# Dummy.net
KiCad netlist of a schematic drawn in EAGLE
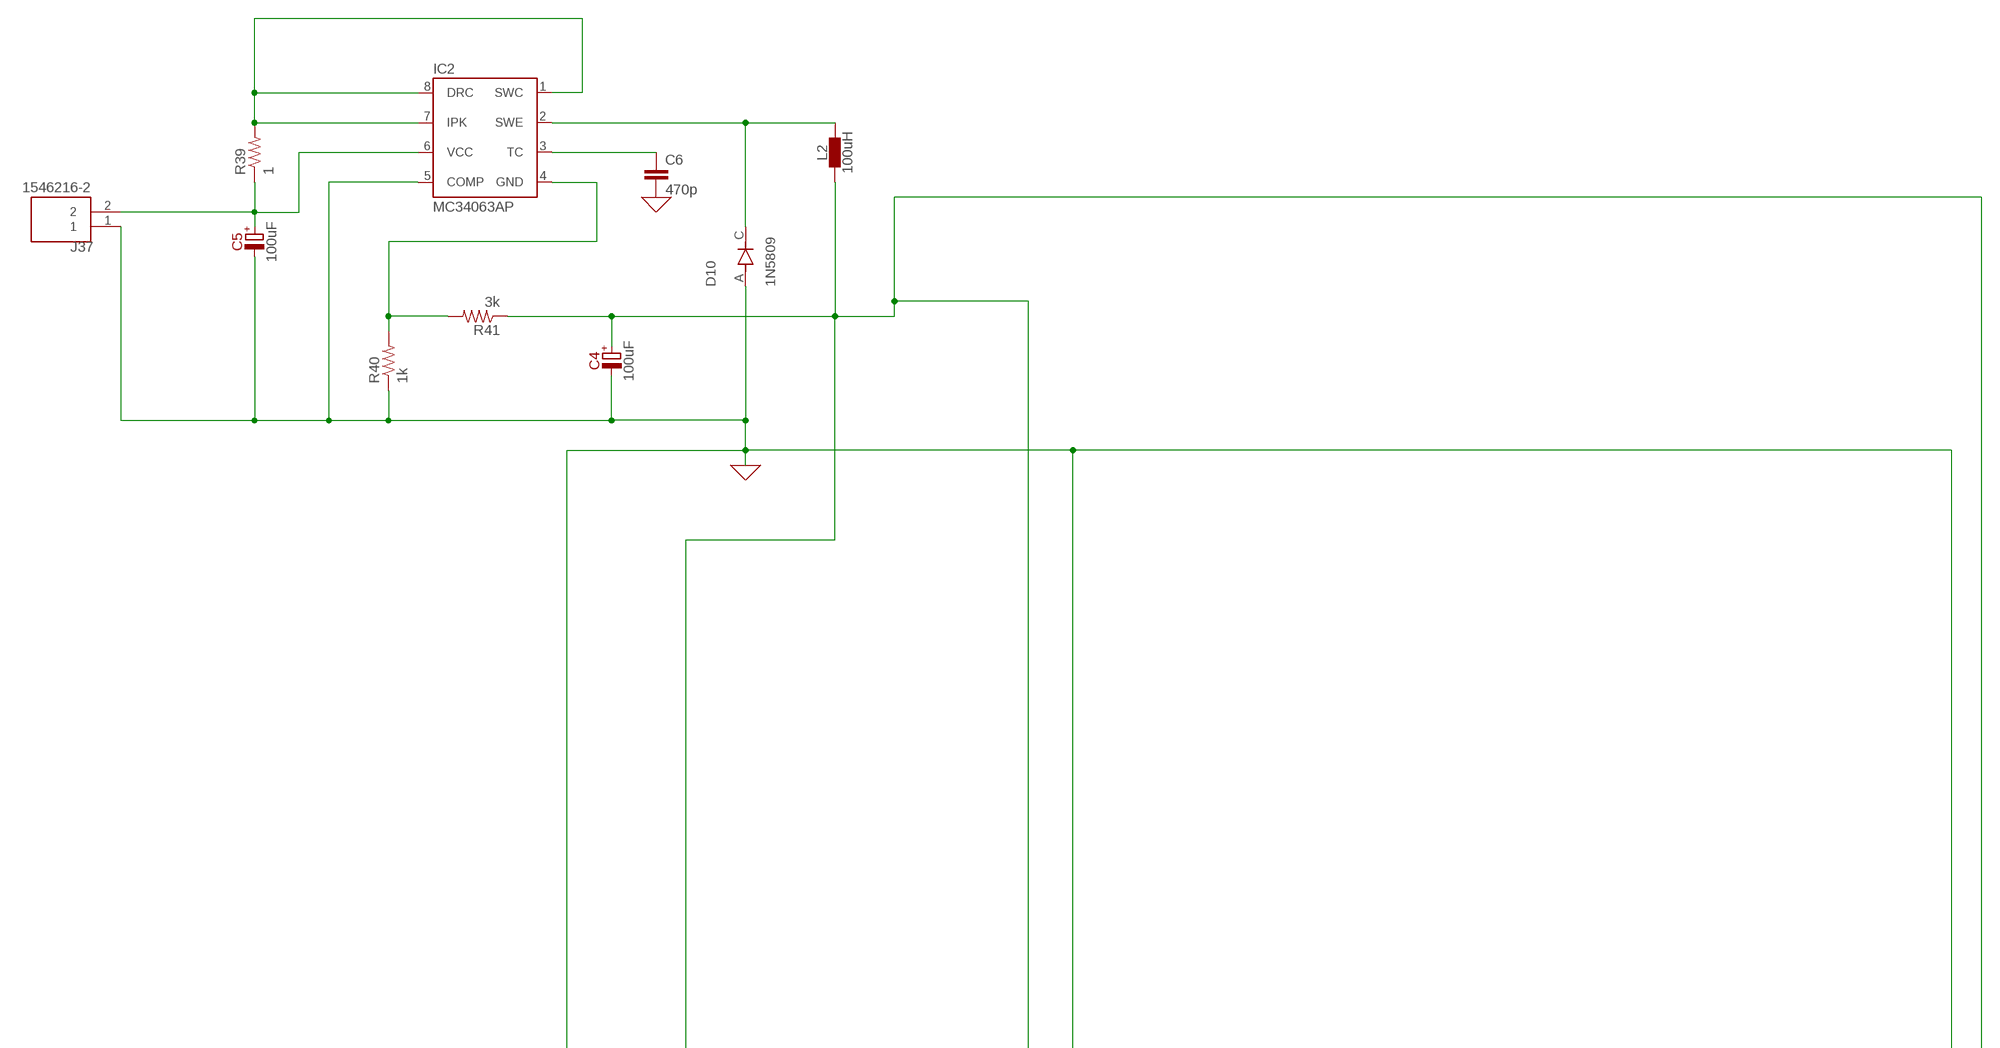
[diagram p0: schematic, sheet 1, part 1 of 3]
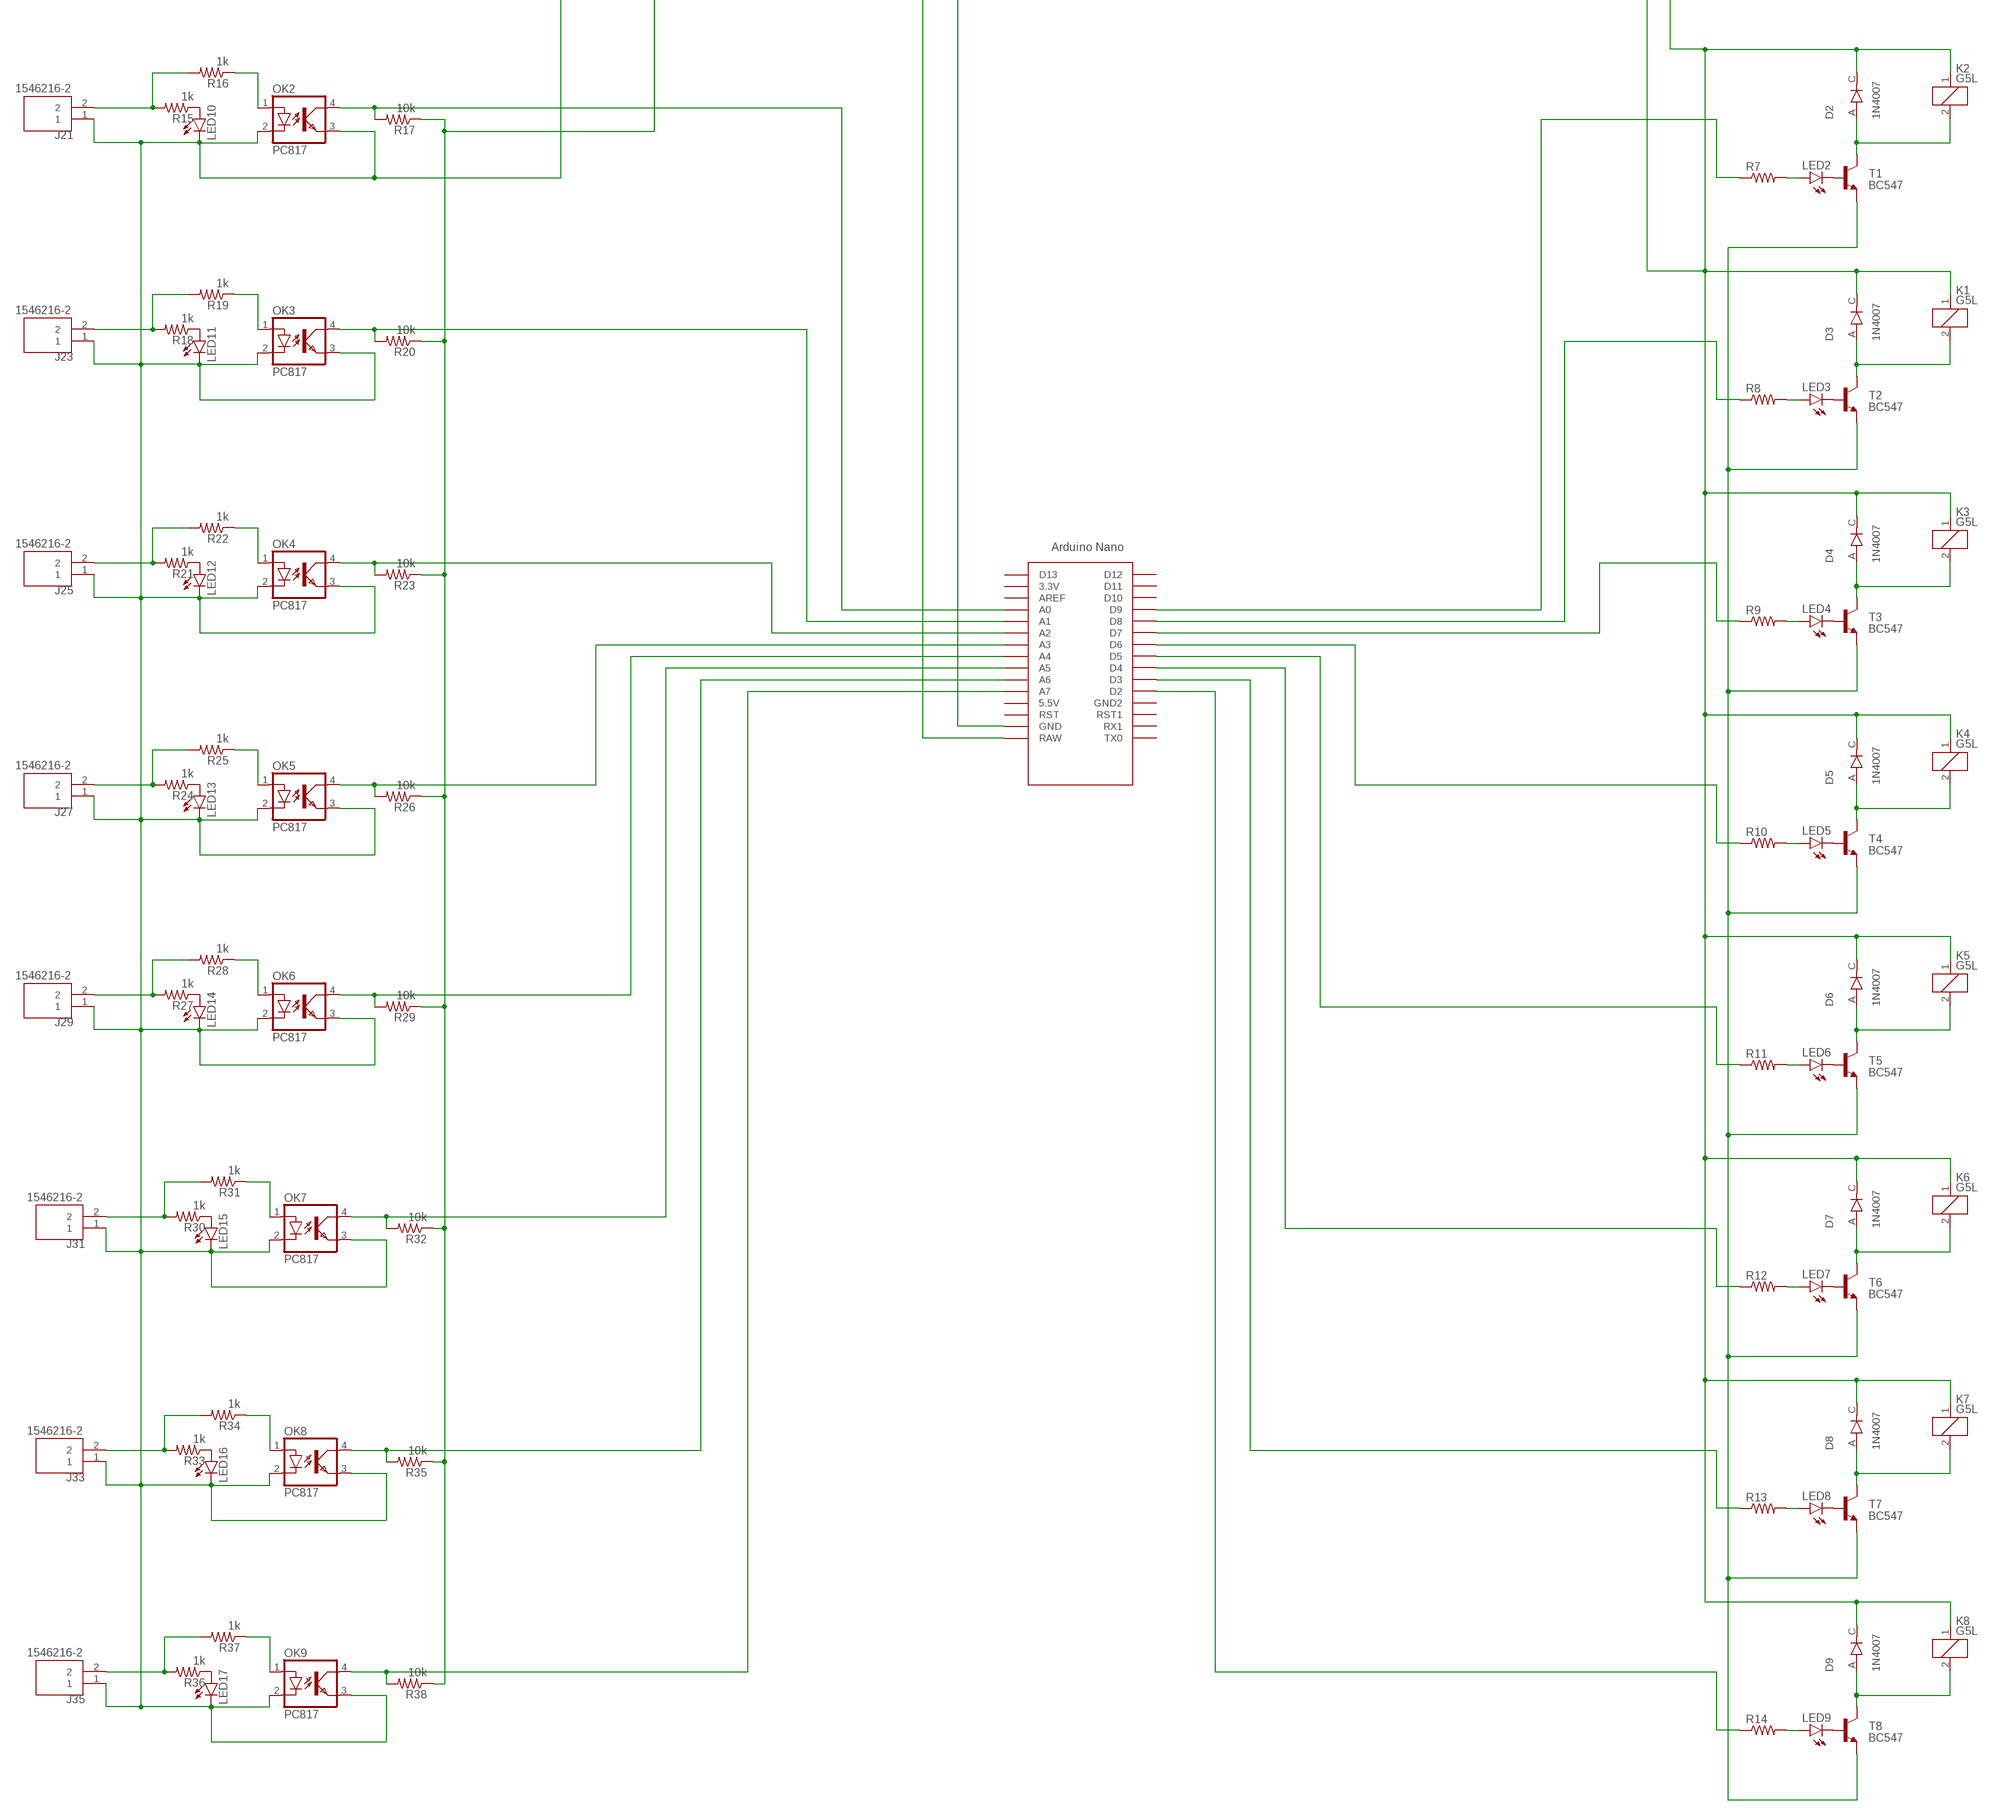
[diagram p1: schematic, sheet 1, part 2 of 3]
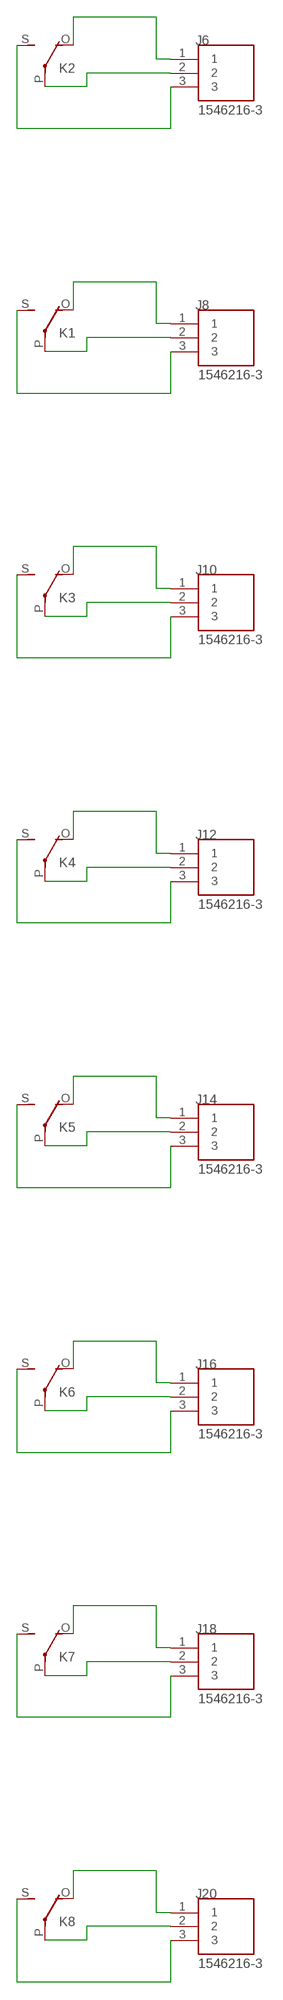
[diagram p2: schematic, sheet 1, part 3 of 3]

(export (version "E")
  (design (tool "Eeschema 10.0.6"))
  (components
    (comp (ref "C4")
      (value "100uF")
      (footprint "eagle-import:E1,5-4")
      (libsource (lib "eagle-import") (part "?1U/50V"))
    )
    (comp (ref "C5")
      (value "100uF")
      (footprint "eagle-import:E1,5-4")
      (libsource (lib "eagle-import") (part "?1U/50V"))
    )
    (comp (ref "C6")
      (value "470p")
      (footprint "eagle-import:C2.5-2")
      (libsource (lib "eagle-import") (part "C2.5/2"))
    )
    (comp (ref "D2")
      (value "1N4007")
      (footprint "eagle-import:DIOAD1060W80L520D270")
      (fields (field (name "MF") "ON Semiconductor"))
      (libsource (lib "eagle-import") (part "1N4007"))
    )
    (comp (ref "D3")
      (value "1N4007")
      (footprint "eagle-import:DIOAD1060W80L520D270")
      (fields (field (name "MF") "ON Semiconductor"))
      (libsource (lib "eagle-import") (part "1N4007"))
    )
    (comp (ref "D4")
      (value "1N4007")
      (footprint "eagle-import:DIOAD1060W80L520D270")
      (fields (field (name "MF") "ON Semiconductor"))
      (libsource (lib "eagle-import") (part "1N4007"))
    )
    (comp (ref "D5")
      (value "1N4007")
      (footprint "eagle-import:DIOAD1060W80L520D270")
      (fields (field (name "MF") "ON Semiconductor"))
      (libsource (lib "eagle-import") (part "1N4007"))
    )
    (comp (ref "D6")
      (value "1N4007")
      (footprint "eagle-import:DIOAD1060W80L520D270")
      (fields (field (name "MF") "ON Semiconductor"))
      (libsource (lib "eagle-import") (part "1N4007"))
    )
    (comp (ref "D7")
      (value "1N4007")
      (footprint "eagle-import:DIOAD1060W80L520D270")
      (fields (field (name "MF") "ON Semiconductor"))
      (libsource (lib "eagle-import") (part "1N4007"))
    )
    (comp (ref "D8")
      (value "1N4007")
      (footprint "eagle-import:DIOAD1060W80L520D270")
      (fields (field (name "MF") "ON Semiconductor"))
      (libsource (lib "eagle-import") (part "1N4007"))
    )
    (comp (ref "D9")
      (value "1N4007")
      (footprint "eagle-import:DIOAD1060W80L520D270")
      (fields (field (name "MF") "ON Semiconductor"))
      (libsource (lib "eagle-import") (part "1N4007"))
    )
    (comp (ref "D10")
      (value "1N5809")
      (footprint "eagle-import:DIOAD1060W80L520D270")
      (fields (field (name "MF") "ON Semiconductor") (field (name "MP") "1N4007"))
      (libsource (lib "eagle-import") (part "1N4007"))
    )
    (comp (ref "IC2")
      (value "MC34063AP")
      (footprint "eagle-import:DIL-08")
      (fields (field (name "MF") "Texas Instruments") (field (name "MP") "MC34063A"))
      (libsource (lib "eagle-import") (part "MC34063AP"))
    )
    (comp (ref "J6")
      (value "1546216-3")
      (footprint "eagle-import:TE_1546216-3")
      (fields (field (name "MF") "TE Connectivity"))
      (libsource (lib "eagle-import") (part "1546216-3"))
    )
    (comp (ref "J8")
      (value "1546216-3")
      (footprint "eagle-import:TE_1546216-3")
      (fields (field (name "MF") "TE Connectivity"))
      (libsource (lib "eagle-import") (part "1546216-3"))
    )
    (comp (ref "J10")
      (value "1546216-3")
      (footprint "eagle-import:TE_1546216-3")
      (fields (field (name "MF") "TE Connectivity"))
      (libsource (lib "eagle-import") (part "1546216-3"))
    )
    (comp (ref "J12")
      (value "1546216-3")
      (footprint "eagle-import:TE_1546216-3")
      (fields (field (name "MF") "TE Connectivity"))
      (libsource (lib "eagle-import") (part "1546216-3"))
    )
    (comp (ref "J14")
      (value "1546216-3")
      (footprint "eagle-import:TE_1546216-3")
      (fields (field (name "MF") "TE Connectivity"))
      (libsource (lib "eagle-import") (part "1546216-3"))
    )
    (comp (ref "J16")
      (value "1546216-3")
      (footprint "eagle-import:TE_1546216-3")
      (fields (field (name "MF") "TE Connectivity"))
      (libsource (lib "eagle-import") (part "1546216-3"))
    )
    (comp (ref "J18")
      (value "1546216-3")
      (footprint "eagle-import:TE_1546216-3")
      (fields (field (name "MF") "TE Connectivity"))
      (libsource (lib "eagle-import") (part "1546216-3"))
    )
    (comp (ref "J20")
      (value "1546216-3")
      (footprint "eagle-import:TE_1546216-3")
      (fields (field (name "MF") "TE Connectivity"))
      (libsource (lib "eagle-import") (part "1546216-3"))
    )
    (comp (ref "J21")
      (value "1546216-2")
      (footprint "eagle-import:TE_1546216-2")
      (fields (field (name "MF") "TE Connectivity"))
      (libsource (lib "eagle-import") (part "1546216-2"))
    )
    (comp (ref "J23")
      (value "1546216-2")
      (footprint "eagle-import:TE_1546216-2")
      (fields (field (name "MF") "TE Connectivity"))
      (libsource (lib "eagle-import") (part "1546216-2"))
    )
    (comp (ref "J25")
      (value "1546216-2")
      (footprint "eagle-import:TE_1546216-2")
      (fields (field (name "MF") "TE Connectivity"))
      (libsource (lib "eagle-import") (part "1546216-2"))
    )
    (comp (ref "J27")
      (value "1546216-2")
      (footprint "eagle-import:TE_1546216-2")
      (fields (field (name "MF") "TE Connectivity"))
      (libsource (lib "eagle-import") (part "1546216-2"))
    )
    (comp (ref "J29")
      (value "1546216-2")
      (footprint "eagle-import:TE_1546216-2")
      (fields (field (name "MF") "TE Connectivity"))
      (libsource (lib "eagle-import") (part "1546216-2"))
    )
    (comp (ref "J31")
      (value "1546216-2")
      (footprint "eagle-import:TE_1546216-2")
      (fields (field (name "MF") "TE Connectivity"))
      (libsource (lib "eagle-import") (part "1546216-2"))
    )
    (comp (ref "J33")
      (value "1546216-2")
      (footprint "eagle-import:TE_1546216-2")
      (fields (field (name "MF") "TE Connectivity"))
      (libsource (lib "eagle-import") (part "1546216-2"))
    )
    (comp (ref "J35")
      (value "1546216-2")
      (footprint "eagle-import:TE_1546216-2")
      (fields (field (name "MF") "TE Connectivity"))
      (libsource (lib "eagle-import") (part "1546216-2"))
    )
    (comp (ref "J37")
      (value "1546216-2")
      (footprint "eagle-import:TE_1546216-2")
      (fields (field (name "MF") "TE Connectivity"))
      (libsource (lib "eagle-import") (part "1546216-2"))
    )
    (comp (ref "K1")
      (value "G5L")
      (footprint "eagle-import:G5LE")
      (libsource (lib "eagle-import") (part "G5L"))
    )
    (comp (ref "K2")
      (value "G5L")
      (footprint "eagle-import:G5LE")
      (libsource (lib "eagle-import") (part "G5L"))
    )
    (comp (ref "K3")
      (value "G5L")
      (footprint "eagle-import:G5LE")
      (libsource (lib "eagle-import") (part "G5L"))
    )
    (comp (ref "K4")
      (value "G5L")
      (footprint "eagle-import:G5LE")
      (libsource (lib "eagle-import") (part "G5L"))
    )
    (comp (ref "K5")
      (value "G5L")
      (footprint "eagle-import:G5LE")
      (libsource (lib "eagle-import") (part "G5L"))
    )
    (comp (ref "K6")
      (value "G5L")
      (footprint "eagle-import:G5LE")
      (libsource (lib "eagle-import") (part "G5L"))
    )
    (comp (ref "K7")
      (value "G5L")
      (footprint "eagle-import:G5LE")
      (libsource (lib "eagle-import") (part "G5L"))
    )
    (comp (ref "K8")
      (value "G5L")
      (footprint "eagle-import:G5LE")
      (libsource (lib "eagle-import") (part "G5L"))
    )
    (comp (ref "L2")
      (value "100uH")
      (footprint "eagle-import:L_NR80XX")
      (libsource (lib "eagle-import") (part "INDUCTOR-NR80XX"))
    )
    (comp (ref "LED2")
      (value "LED3MM")
      (footprint "eagle-import:LED3MM")
      (libsource (lib "eagle-import") (part "LED3MM"))
    )
    (comp (ref "LED3")
      (value "LED3MM")
      (footprint "eagle-import:LED3MM")
      (libsource (lib "eagle-import") (part "LED3MM"))
    )
    (comp (ref "LED4")
      (value "LED3MM")
      (footprint "eagle-import:LED3MM")
      (libsource (lib "eagle-import") (part "LED3MM"))
    )
    (comp (ref "LED5")
      (value "LED3MM")
      (footprint "eagle-import:LED3MM")
      (libsource (lib "eagle-import") (part "LED3MM"))
    )
    (comp (ref "LED6")
      (value "LED3MM")
      (footprint "eagle-import:LED3MM")
      (libsource (lib "eagle-import") (part "LED3MM"))
    )
    (comp (ref "LED7")
      (value "LED3MM")
      (footprint "eagle-import:LED3MM")
      (libsource (lib "eagle-import") (part "LED3MM"))
    )
    (comp (ref "LED8")
      (value "LED3MM")
      (footprint "eagle-import:LED3MM")
      (libsource (lib "eagle-import") (part "LED3MM"))
    )
    (comp (ref "LED9")
      (value "LED3MM")
      (footprint "eagle-import:LED3MM")
      (libsource (lib "eagle-import") (part "LED3MM"))
    )
    (comp (ref "LED10")
      (value "LED3MM")
      (footprint "eagle-import:LED3MM")
      (libsource (lib "eagle-import") (part "LED3MM"))
    )
    (comp (ref "LED11")
      (value "LED3MM")
      (footprint "eagle-import:LED3MM")
      (libsource (lib "eagle-import") (part "LED3MM"))
    )
    (comp (ref "LED12")
      (value "LED3MM")
      (footprint "eagle-import:LED3MM")
      (libsource (lib "eagle-import") (part "LED3MM"))
    )
    (comp (ref "LED13")
      (value "LED3MM")
      (footprint "eagle-import:LED3MM")
      (libsource (lib "eagle-import") (part "LED3MM"))
    )
    (comp (ref "LED14")
      (value "LED3MM")
      (footprint "eagle-import:LED3MM")
      (libsource (lib "eagle-import") (part "LED3MM"))
    )
    (comp (ref "LED15")
      (value "LED3MM")
      (footprint "eagle-import:LED3MM")
      (libsource (lib "eagle-import") (part "LED3MM"))
    )
    (comp (ref "LED16")
      (value "LED3MM")
      (footprint "eagle-import:LED3MM")
      (libsource (lib "eagle-import") (part "LED3MM"))
    )
    (comp (ref "LED17")
      (value "LED3MM")
      (footprint "eagle-import:LED3MM")
      (libsource (lib "eagle-import") (part "LED3MM"))
    )
    (comp (ref "OK2")
      (value "PC817")
      (footprint "eagle-import:DIL04")
      (fields (field (name "MPN") "PC817X4J000F"))
      (libsource (lib "eagle-import") (part "PC817"))
    )
    (comp (ref "OK3")
      (value "PC817")
      (footprint "eagle-import:DIL04")
      (fields (field (name "MPN") "PC817X4J000F"))
      (libsource (lib "eagle-import") (part "PC817"))
    )
    (comp (ref "OK4")
      (value "PC817")
      (footprint "eagle-import:DIL04")
      (fields (field (name "MPN") "PC817X4J000F"))
      (libsource (lib "eagle-import") (part "PC817"))
    )
    (comp (ref "OK5")
      (value "PC817")
      (footprint "eagle-import:DIL04")
      (fields (field (name "MPN") "PC817X4J000F"))
      (libsource (lib "eagle-import") (part "PC817"))
    )
    (comp (ref "OK6")
      (value "PC817")
      (footprint "eagle-import:DIL04")
      (fields (field (name "MPN") "PC817X4J000F"))
      (libsource (lib "eagle-import") (part "PC817"))
    )
    (comp (ref "OK7")
      (value "PC817")
      (footprint "eagle-import:DIL04")
      (fields (field (name "MPN") "PC817X4J000F"))
      (libsource (lib "eagle-import") (part "PC817"))
    )
    (comp (ref "OK8")
      (value "PC817")
      (footprint "eagle-import:DIL04")
      (fields (field (name "MPN") "PC817X4J000F"))
      (libsource (lib "eagle-import") (part "PC817"))
    )
    (comp (ref "OK9")
      (value "PC817")
      (footprint "eagle-import:DIL04")
      (fields (field (name "MPN") "PC817X4J000F"))
      (libsource (lib "eagle-import") (part "PC817"))
    )
    (comp (ref "R7")
      (value "R-US_0207/15")
      (footprint "eagle-import:0207_15")
      (libsource (lib "eagle-import") (part "resistor_348_R-US_0207/15"))
    )
    (comp (ref "R8")
      (value "R-US_0207/15")
      (footprint "eagle-import:0207_15")
      (libsource (lib "eagle-import") (part "resistor_348_R-US_0207/15"))
    )
    (comp (ref "R9")
      (value "R-US_0207/15")
      (footprint "eagle-import:0207_15")
      (libsource (lib "eagle-import") (part "resistor_348_R-US_0207/15"))
    )
    (comp (ref "R10")
      (value "R-US_0207/15")
      (footprint "eagle-import:0207_15")
      (libsource (lib "eagle-import") (part "resistor_348_R-US_0207/15"))
    )
    (comp (ref "R11")
      (value "R-US_0207/15")
      (footprint "eagle-import:0207_15")
      (libsource (lib "eagle-import") (part "resistor_348_R-US_0207/15"))
    )
    (comp (ref "R12")
      (value "R-US_0207/15")
      (footprint "eagle-import:0207_15")
      (libsource (lib "eagle-import") (part "resistor_348_R-US_0207/15"))
    )
    (comp (ref "R13")
      (value "R-US_0207/15")
      (footprint "eagle-import:0207_15")
      (libsource (lib "eagle-import") (part "resistor_348_R-US_0207/15"))
    )
    (comp (ref "R14")
      (value "R-US_0207/15")
      (footprint "eagle-import:0207_15")
      (libsource (lib "eagle-import") (part "resistor_348_R-US_0207/15"))
    )
    (comp (ref "R15")
      (value "1k")
      (footprint "eagle-import:0207_15")
      (libsource (lib "eagle-import") (part "R-US_0207/15"))
    )
    (comp (ref "R16")
      (value "1k")
      (footprint "eagle-import:0207_15")
      (libsource (lib "eagle-import") (part "R-US_0207/15"))
    )
    (comp (ref "R17")
      (value "10k")
      (footprint "eagle-import:0207_15")
      (libsource (lib "eagle-import") (part "R-US_0207/15"))
    )
    (comp (ref "R18")
      (value "1k")
      (footprint "eagle-import:0207_15")
      (libsource (lib "eagle-import") (part "R-US_0207/15"))
    )
    (comp (ref "R19")
      (value "1k")
      (footprint "eagle-import:0207_15")
      (libsource (lib "eagle-import") (part "R-US_0207/15"))
    )
    (comp (ref "R20")
      (value "10k")
      (footprint "eagle-import:0207_15")
      (libsource (lib "eagle-import") (part "R-US_0207/15"))
    )
    (comp (ref "R21")
      (value "1k")
      (footprint "eagle-import:0207_15")
      (libsource (lib "eagle-import") (part "R-US_0207/15"))
    )
    (comp (ref "R22")
      (value "1k")
      (footprint "eagle-import:0207_15")
      (libsource (lib "eagle-import") (part "R-US_0207/15"))
    )
    (comp (ref "R23")
      (value "10k")
      (footprint "eagle-import:0207_15")
      (libsource (lib "eagle-import") (part "R-US_0207/15"))
    )
    (comp (ref "R24")
      (value "1k")
      (footprint "eagle-import:0207_15")
      (libsource (lib "eagle-import") (part "R-US_0207/15"))
    )
    (comp (ref "R25")
      (value "1k")
      (footprint "eagle-import:0207_15")
      (libsource (lib "eagle-import") (part "R-US_0207/15"))
    )
    (comp (ref "R26")
      (value "10k")
      (footprint "eagle-import:0207_15")
      (libsource (lib "eagle-import") (part "R-US_0207/15"))
    )
    (comp (ref "R27")
      (value "1k")
      (footprint "eagle-import:0207_15")
      (libsource (lib "eagle-import") (part "R-US_0207/15"))
    )
    (comp (ref "R28")
      (value "1k")
      (footprint "eagle-import:0207_15")
      (libsource (lib "eagle-import") (part "R-US_0207/15"))
    )
    (comp (ref "R29")
      (value "10k")
      (footprint "eagle-import:0207_15")
      (libsource (lib "eagle-import") (part "R-US_0207/15"))
    )
    (comp (ref "R30")
      (value "1k")
      (footprint "eagle-import:0207_15")
      (libsource (lib "eagle-import") (part "R-US_0207/15"))
    )
    (comp (ref "R31")
      (value "1k")
      (footprint "eagle-import:0207_15")
      (libsource (lib "eagle-import") (part "R-US_0207/15"))
    )
    (comp (ref "R32")
      (value "10k")
      (footprint "eagle-import:0207_15")
      (libsource (lib "eagle-import") (part "R-US_0207/15"))
    )
    (comp (ref "R33")
      (value "1k")
      (footprint "eagle-import:0207_15")
      (libsource (lib "eagle-import") (part "R-US_0207/15"))
    )
    (comp (ref "R34")
      (value "1k")
      (footprint "eagle-import:0207_15")
      (libsource (lib "eagle-import") (part "R-US_0207/15"))
    )
    (comp (ref "R35")
      (value "10k")
      (footprint "eagle-import:0207_15")
      (libsource (lib "eagle-import") (part "R-US_0207/15"))
    )
    (comp (ref "R36")
      (value "1k")
      (footprint "eagle-import:0207_15")
      (libsource (lib "eagle-import") (part "R-US_0207/15"))
    )
    (comp (ref "R37")
      (value "1k")
      (footprint "eagle-import:0207_15")
      (libsource (lib "eagle-import") (part "R-US_0207/15"))
    )
    (comp (ref "R38")
      (value "10k")
      (footprint "eagle-import:0207_15")
      (libsource (lib "eagle-import") (part "R-US_0207/15"))
    )
    (comp (ref "R39")
      (value "1")
      (footprint "eagle-import:0207_12")
      (libsource (lib "eagle-import") (part "resistor_348_R-US_0207/12"))
    )
    (comp (ref "R40")
      (value "1k")
      (footprint "eagle-import:0207_12")
      (libsource (lib "eagle-import") (part "resistor_348_R-US_0207/12"))
    )
    (comp (ref "R41")
      (value "3k")
      (footprint "eagle-import:0207_12")
      (libsource (lib "eagle-import") (part "resistor_348_R-US_0207/12"))
    )
    (comp (ref "T1")
      (value "BC547")
      (footprint "eagle-import:TO92")
      (fields (field (name "MF") "ON"))
      (libsource (lib "eagle-import") (part "BC547"))
    )
    (comp (ref "T2")
      (value "BC547")
      (footprint "eagle-import:TO92")
      (fields (field (name "MF") "ON"))
      (libsource (lib "eagle-import") (part "BC547"))
    )
    (comp (ref "T3")
      (value "BC547")
      (footprint "eagle-import:TO92")
      (fields (field (name "MF") "ON"))
      (libsource (lib "eagle-import") (part "BC547"))
    )
    (comp (ref "T4")
      (value "BC547")
      (footprint "eagle-import:TO92")
      (fields (field (name "MF") "ON"))
      (libsource (lib "eagle-import") (part "BC547"))
    )
    (comp (ref "T5")
      (value "BC547")
      (footprint "eagle-import:TO92")
      (fields (field (name "MF") "ON"))
      (libsource (lib "eagle-import") (part "BC547"))
    )
    (comp (ref "T6")
      (value "BC547")
      (footprint "eagle-import:TO92")
      (fields (field (name "MF") "ON"))
      (libsource (lib "eagle-import") (part "BC547"))
    )
    (comp (ref "T7")
      (value "BC547")
      (footprint "eagle-import:TO92")
      (fields (field (name "MF") "ON"))
      (libsource (lib "eagle-import") (part "BC547"))
    )
    (comp (ref "T8")
      (value "BC547")
      (footprint "eagle-import:TO92")
      (fields (field (name "MF") "ON"))
      (libsource (lib "eagle-import") (part "BC547"))
    )
    (comp (ref "U$1")
      (value "NANO")
      (footprint "eagle-import:NANO")
      (libsource (lib "eagle-import") (part "NANO"))
    )
  )
  (nets
    (net (code "1") (name "GND") (class "Default")
      (node (ref "C4") (pin "+") (pinfunction "+_+") (pintype "passive"))
      (node (ref "C4") (pin "-") (pinfunction "-_-") (pintype "passive"))
      (node (ref "C5") (pin "-") (pinfunction "-_-") (pintype "passive"))
      (node (ref "C6") (pin "2") (pinfunction "2_2") (pintype "passive"))
      (node (ref "D10") (pin "A") (pinfunction "A_A") (pintype "passive"))
      (node (ref "D2") (pin "C") (pinfunction "C_C") (pintype "passive"))
      (node (ref "D3") (pin "C") (pinfunction "C_C") (pintype "passive"))
      (node (ref "D4") (pin "C") (pinfunction "C_C") (pintype "passive"))
      (node (ref "D5") (pin "C") (pinfunction "C_C") (pintype "passive"))
      (node (ref "D6") (pin "C") (pinfunction "C_C") (pintype "passive"))
      (node (ref "D7") (pin "C") (pinfunction "C_C") (pintype "passive"))
      (node (ref "D8") (pin "C") (pinfunction "C_C") (pintype "passive"))
      (node (ref "D9") (pin "C") (pinfunction "C_C") (pintype "passive"))
      (node (ref "IC2") (pin "5") (pinfunction "COMP_5") (pintype "input"))
      (node (ref "J21") (pin "1") (pinfunction "1_1") (pintype "passive"))
      (node (ref "J23") (pin "1") (pinfunction "1_1") (pintype "passive"))
      (node (ref "J25") (pin "1") (pinfunction "1_1") (pintype "passive"))
      (node (ref "J27") (pin "1") (pinfunction "1_1") (pintype "passive"))
      (node (ref "J29") (pin "1") (pinfunction "1_1") (pintype "passive"))
      (node (ref "J31") (pin "1") (pinfunction "1_1") (pintype "passive"))
      (node (ref "J33") (pin "1") (pinfunction "1_1") (pintype "passive"))
      (node (ref "J35") (pin "1") (pinfunction "1_1") (pintype "passive"))
      (node (ref "J37") (pin "1") (pinfunction "1_1") (pintype "passive"))
      (node (ref "K1") (pin "1") (pinfunction "1_1") (pintype "passive"))
      (node (ref "K2") (pin "1") (pinfunction "1_1") (pintype "passive"))
      (node (ref "K3") (pin "1") (pinfunction "1_1") (pintype "passive"))
      (node (ref "K4") (pin "1") (pinfunction "1_1") (pintype "passive"))
      (node (ref "K5") (pin "1") (pinfunction "1_1") (pintype "passive"))
      (node (ref "K6") (pin "1") (pinfunction "1_1") (pintype "passive"))
      (node (ref "K7") (pin "1") (pinfunction "1_1") (pintype "passive"))
      (node (ref "K8") (pin "1") (pinfunction "1_1") (pintype "passive"))
      (node (ref "L2") (pin "1") (pinfunction "1_1") (pintype "passive"))
      (node (ref "LED10") (pin "K") (pinfunction "C_K") (pintype "passive"))
      (node (ref "LED11") (pin "K") (pinfunction "C_K") (pintype "passive"))
      (node (ref "LED12") (pin "K") (pinfunction "C_K") (pintype "passive"))
      (node (ref "LED13") (pin "K") (pinfunction "C_K") (pintype "passive"))
      (node (ref "LED14") (pin "K") (pinfunction "C_K") (pintype "passive"))
      (node (ref "LED15") (pin "K") (pinfunction "C_K") (pintype "passive"))
      (node (ref "LED16") (pin "K") (pinfunction "C_K") (pintype "passive"))
      (node (ref "LED17") (pin "K") (pinfunction "C_K") (pintype "passive"))
      (node (ref "OK2") (pin "2") (pinfunction "C_2") (pintype "passive"))
      (node (ref "OK2") (pin "3") (pinfunction "EMIT_3") (pintype "passive"))
      (node (ref "OK3") (pin "2") (pinfunction "C_2") (pintype "passive"))
      (node (ref "OK3") (pin "3") (pinfunction "EMIT_3") (pintype "passive"))
      (node (ref "OK4") (pin "2") (pinfunction "C_2") (pintype "passive"))
      (node (ref "OK4") (pin "3") (pinfunction "EMIT_3") (pintype "passive"))
      (node (ref "OK5") (pin "2") (pinfunction "C_2") (pintype "passive"))
      (node (ref "OK5") (pin "3") (pinfunction "EMIT_3") (pintype "passive"))
      (node (ref "OK6") (pin "2") (pinfunction "C_2") (pintype "passive"))
      (node (ref "OK6") (pin "3") (pinfunction "EMIT_3") (pintype "passive"))
      (node (ref "OK7") (pin "2") (pinfunction "C_2") (pintype "passive"))
      (node (ref "OK7") (pin "3") (pinfunction "EMIT_3") (pintype "passive"))
      (node (ref "OK8") (pin "2") (pinfunction "C_2") (pintype "passive"))
      (node (ref "OK8") (pin "3") (pinfunction "EMIT_3") (pintype "passive"))
      (node (ref "OK9") (pin "2") (pinfunction "C_2") (pintype "passive"))
      (node (ref "OK9") (pin "3") (pinfunction "EMIT_3") (pintype "passive"))
      (node (ref "R17") (pin "1") (pinfunction "1_1") (pintype "passive"))
      (node (ref "R20") (pin "1") (pinfunction "1_1") (pintype "passive"))
      (node (ref "R23") (pin "1") (pinfunction "1_1") (pintype "passive"))
      (node (ref "R26") (pin "1") (pinfunction "1_1") (pintype "passive"))
      (node (ref "R29") (pin "1") (pinfunction "1_1") (pintype "passive"))
      (node (ref "R32") (pin "1") (pinfunction "1_1") (pintype "passive"))
      (node (ref "R35") (pin "1") (pinfunction "1_1") (pintype "passive"))
      (node (ref "R38") (pin "1") (pinfunction "1_1") (pintype "passive"))
      (node (ref "R40") (pin "1") (pinfunction "1_1") (pintype "passive"))
      (node (ref "R41") (pin "1") (pinfunction "1_1") (pintype "passive"))
      (node (ref "U$1") (pin "GND") (pinfunction "GND_GND") (pintype "bidirectional"))
      (node (ref "U$1") (pin "RAW") (pinfunction "RAW_RAW") (pintype "bidirectional"))
    )
    (net (code "2") (name "Net-(IC2-DRC)") (class "Default")
      (node (ref "IC2") (pin "1") (pinfunction "SWC_1") (pintype "bidirectional"))
      (node (ref "IC2") (pin "7") (pinfunction "IPK_7") (pintype "input"))
      (node (ref "IC2") (pin "8") (pinfunction "DRC_8") (pintype "input"))
      (node (ref "R39") (pin "2") (pinfunction "2_2") (pintype "passive"))
    )
    (net (code "3") (name "Net-(IC2-GND)") (class "Default")
      (node (ref "IC2") (pin "4") (pinfunction "GND_4") (pintype "power_in"))
      (node (ref "R40") (pin "2") (pinfunction "2_2") (pintype "passive"))
      (node (ref "R41") (pin "2") (pinfunction "2_2") (pintype "passive"))
    )
    (net (code "4") (name "Net-(IC2-SWE)") (class "Default")
      (node (ref "D10") (pin "C") (pinfunction "C_C") (pintype "passive"))
      (node (ref "IC2") (pin "2") (pinfunction "SWE_2") (pintype "bidirectional"))
      (node (ref "L2") (pin "2") (pinfunction "2_2") (pintype "passive"))
    )
    (net (code "5") (name "Net-(IC2-TC)") (class "Default")
      (node (ref "C6") (pin "1") (pinfunction "1_1") (pintype "passive"))
      (node (ref "IC2") (pin "3") (pinfunction "TC_3") (pintype "passive"))
    )
    (net (code "6") (name "Net-(IC2-VCC)") (class "Default")
      (node (ref "C5") (pin "+") (pinfunction "+_+") (pintype "passive"))
      (node (ref "IC2") (pin "6") (pinfunction "VCC_6") (pintype "power_in"))
      (node (ref "J37") (pin "2") (pinfunction "2_2") (pintype "passive"))
      (node (ref "R39") (pin "1") (pinfunction "1_1") (pintype "passive"))
    )
    (net (code "7") (name "Net-(J6-Pad1)") (class "Default")
      (node (ref "J6") (pin "1") (pinfunction "1_1") (pintype "passive"))
      (node (ref "K2") (pin "O") (pinfunction "O_O") (pintype "passive"))
    )
    (net (code "8") (name "Net-(J6-Pad2)") (class "Default")
      (node (ref "J6") (pin "2") (pinfunction "2_2") (pintype "passive"))
      (node (ref "K2") (pin "P") (pinfunction "P_P") (pintype "passive"))
    )
    (net (code "9") (name "Net-(J6-Pad3)") (class "Default")
      (node (ref "J6") (pin "3") (pinfunction "3_3") (pintype "passive"))
      (node (ref "K2") (pin "S") (pinfunction "S_S") (pintype "passive"))
    )
    (net (code "10") (name "Net-(J8-Pad1)") (class "Default")
      (node (ref "J8") (pin "1") (pinfunction "1_1") (pintype "passive"))
      (node (ref "K1") (pin "O") (pinfunction "O_O") (pintype "passive"))
    )
    (net (code "11") (name "Net-(J8-Pad2)") (class "Default")
      (node (ref "J8") (pin "2") (pinfunction "2_2") (pintype "passive"))
      (node (ref "K1") (pin "P") (pinfunction "P_P") (pintype "passive"))
    )
    (net (code "12") (name "Net-(J8-Pad3)") (class "Default")
      (node (ref "J8") (pin "3") (pinfunction "3_3") (pintype "passive"))
      (node (ref "K1") (pin "S") (pinfunction "S_S") (pintype "passive"))
    )
    (net (code "13") (name "Net-(J10-Pad1)") (class "Default")
      (node (ref "J10") (pin "1") (pinfunction "1_1") (pintype "passive"))
      (node (ref "K3") (pin "O") (pinfunction "O_O") (pintype "passive"))
    )
    (net (code "14") (name "Net-(J10-Pad2)") (class "Default")
      (node (ref "J10") (pin "2") (pinfunction "2_2") (pintype "passive"))
      (node (ref "K3") (pin "P") (pinfunction "P_P") (pintype "passive"))
    )
    (net (code "15") (name "Net-(J10-Pad3)") (class "Default")
      (node (ref "J10") (pin "3") (pinfunction "3_3") (pintype "passive"))
      (node (ref "K3") (pin "S") (pinfunction "S_S") (pintype "passive"))
    )
    (net (code "16") (name "Net-(J12-Pad1)") (class "Default")
      (node (ref "J12") (pin "1") (pinfunction "1_1") (pintype "passive"))
      (node (ref "K4") (pin "O") (pinfunction "O_O") (pintype "passive"))
    )
    (net (code "17") (name "Net-(J12-Pad2)") (class "Default")
      (node (ref "J12") (pin "2") (pinfunction "2_2") (pintype "passive"))
      (node (ref "K4") (pin "P") (pinfunction "P_P") (pintype "passive"))
    )
    (net (code "18") (name "Net-(J12-Pad3)") (class "Default")
      (node (ref "J12") (pin "3") (pinfunction "3_3") (pintype "passive"))
      (node (ref "K4") (pin "S") (pinfunction "S_S") (pintype "passive"))
    )
    (net (code "19") (name "Net-(J14-Pad1)") (class "Default")
      (node (ref "J14") (pin "1") (pinfunction "1_1") (pintype "passive"))
      (node (ref "K5") (pin "O") (pinfunction "O_O") (pintype "passive"))
    )
    (net (code "20") (name "Net-(J14-Pad2)") (class "Default")
      (node (ref "J14") (pin "2") (pinfunction "2_2") (pintype "passive"))
      (node (ref "K5") (pin "P") (pinfunction "P_P") (pintype "passive"))
    )
    (net (code "21") (name "Net-(J14-Pad3)") (class "Default")
      (node (ref "J14") (pin "3") (pinfunction "3_3") (pintype "passive"))
      (node (ref "K5") (pin "S") (pinfunction "S_S") (pintype "passive"))
    )
    (net (code "22") (name "Net-(J16-Pad1)") (class "Default")
      (node (ref "J16") (pin "1") (pinfunction "1_1") (pintype "passive"))
      (node (ref "K6") (pin "O") (pinfunction "O_O") (pintype "passive"))
    )
    (net (code "23") (name "Net-(J16-Pad2)") (class "Default")
      (node (ref "J16") (pin "2") (pinfunction "2_2") (pintype "passive"))
      (node (ref "K6") (pin "P") (pinfunction "P_P") (pintype "passive"))
    )
    (net (code "24") (name "Net-(J16-Pad3)") (class "Default")
      (node (ref "J16") (pin "3") (pinfunction "3_3") (pintype "passive"))
      (node (ref "K6") (pin "S") (pinfunction "S_S") (pintype "passive"))
    )
    (net (code "25") (name "Net-(J18-Pad1)") (class "Default")
      (node (ref "J18") (pin "1") (pinfunction "1_1") (pintype "passive"))
      (node (ref "K7") (pin "O") (pinfunction "O_O") (pintype "passive"))
    )
    (net (code "26") (name "Net-(J18-Pad2)") (class "Default")
      (node (ref "J18") (pin "2") (pinfunction "2_2") (pintype "passive"))
      (node (ref "K7") (pin "P") (pinfunction "P_P") (pintype "passive"))
    )
    (net (code "27") (name "Net-(J18-Pad3)") (class "Default")
      (node (ref "J18") (pin "3") (pinfunction "3_3") (pintype "passive"))
      (node (ref "K7") (pin "S") (pinfunction "S_S") (pintype "passive"))
    )
    (net (code "28") (name "Net-(J20-Pad1)") (class "Default")
      (node (ref "J20") (pin "1") (pinfunction "1_1") (pintype "passive"))
      (node (ref "K8") (pin "O") (pinfunction "O_O") (pintype "passive"))
    )
    (net (code "29") (name "Net-(J20-Pad2)") (class "Default")
      (node (ref "J20") (pin "2") (pinfunction "2_2") (pintype "passive"))
      (node (ref "K8") (pin "P") (pinfunction "P_P") (pintype "passive"))
    )
    (net (code "30") (name "Net-(J20-Pad3)") (class "Default")
      (node (ref "J20") (pin "3") (pinfunction "3_3") (pintype "passive"))
      (node (ref "K8") (pin "S") (pinfunction "S_S") (pintype "passive"))
    )
    (net (code "31") (name "Net-(J21-Pad2)") (class "Default")
      (node (ref "J21") (pin "2") (pinfunction "2_2") (pintype "passive"))
      (node (ref "R15") (pin "2") (pinfunction "2_2") (pintype "passive"))
      (node (ref "R16") (pin "2") (pinfunction "2_2") (pintype "passive"))
    )
    (net (code "32") (name "Net-(J23-Pad2)") (class "Default")
      (node (ref "J23") (pin "2") (pinfunction "2_2") (pintype "passive"))
      (node (ref "R18") (pin "2") (pinfunction "2_2") (pintype "passive"))
      (node (ref "R19") (pin "2") (pinfunction "2_2") (pintype "passive"))
    )
    (net (code "33") (name "Net-(J25-Pad2)") (class "Default")
      (node (ref "J25") (pin "2") (pinfunction "2_2") (pintype "passive"))
      (node (ref "R21") (pin "2") (pinfunction "2_2") (pintype "passive"))
      (node (ref "R22") (pin "2") (pinfunction "2_2") (pintype "passive"))
    )
    (net (code "34") (name "Net-(J27-Pad2)") (class "Default")
      (node (ref "J27") (pin "2") (pinfunction "2_2") (pintype "passive"))
      (node (ref "R24") (pin "2") (pinfunction "2_2") (pintype "passive"))
      (node (ref "R25") (pin "2") (pinfunction "2_2") (pintype "passive"))
    )
    (net (code "35") (name "Net-(J29-Pad2)") (class "Default")
      (node (ref "J29") (pin "2") (pinfunction "2_2") (pintype "passive"))
      (node (ref "R27") (pin "2") (pinfunction "2_2") (pintype "passive"))
      (node (ref "R28") (pin "2") (pinfunction "2_2") (pintype "passive"))
    )
    (net (code "36") (name "Net-(J31-Pad2)") (class "Default")
      (node (ref "J31") (pin "2") (pinfunction "2_2") (pintype "passive"))
      (node (ref "R30") (pin "2") (pinfunction "2_2") (pintype "passive"))
      (node (ref "R31") (pin "2") (pinfunction "2_2") (pintype "passive"))
    )
    (net (code "37") (name "Net-(J33-Pad2)") (class "Default")
      (node (ref "J33") (pin "2") (pinfunction "2_2") (pintype "passive"))
      (node (ref "R33") (pin "2") (pinfunction "2_2") (pintype "passive"))
      (node (ref "R34") (pin "2") (pinfunction "2_2") (pintype "passive"))
    )
    (net (code "38") (name "Net-(J35-Pad2)") (class "Default")
      (node (ref "J35") (pin "2") (pinfunction "2_2") (pintype "passive"))
      (node (ref "R36") (pin "2") (pinfunction "2_2") (pintype "passive"))
      (node (ref "R37") (pin "2") (pinfunction "2_2") (pintype "passive"))
    )
    (net (code "39") (name "Net-(LED2-C)") (class "Default")
      (node (ref "LED2") (pin "K") (pinfunction "C_K") (pintype "passive"))
      (node (ref "T1") (pin "2") (pinfunction "B_2") (pintype "passive"))
    )
    (net (code "40") (name "Net-(LED2-PadA)") (class "Default")
      (node (ref "LED2") (pin "A") (pinfunction "A_A") (pintype "passive"))
      (node (ref "R7") (pin "2") (pinfunction "2_2") (pintype "passive"))
    )
    (net (code "41") (name "Net-(LED3-C)") (class "Default")
      (node (ref "LED3") (pin "K") (pinfunction "C_K") (pintype "passive"))
      (node (ref "T2") (pin "2") (pinfunction "B_2") (pintype "passive"))
    )
    (net (code "42") (name "Net-(LED3-PadA)") (class "Default")
      (node (ref "LED3") (pin "A") (pinfunction "A_A") (pintype "passive"))
      (node (ref "R8") (pin "2") (pinfunction "2_2") (pintype "passive"))
    )
    (net (code "43") (name "Net-(LED4-C)") (class "Default")
      (node (ref "LED4") (pin "K") (pinfunction "C_K") (pintype "passive"))
      (node (ref "T3") (pin "2") (pinfunction "B_2") (pintype "passive"))
    )
    (net (code "44") (name "Net-(LED4-PadA)") (class "Default")
      (node (ref "LED4") (pin "A") (pinfunction "A_A") (pintype "passive"))
      (node (ref "R9") (pin "2") (pinfunction "2_2") (pintype "passive"))
    )
    (net (code "45") (name "Net-(LED5-C)") (class "Default")
      (node (ref "LED5") (pin "K") (pinfunction "C_K") (pintype "passive"))
      (node (ref "T4") (pin "2") (pinfunction "B_2") (pintype "passive"))
    )
    (net (code "46") (name "Net-(LED5-PadA)") (class "Default")
      (node (ref "LED5") (pin "A") (pinfunction "A_A") (pintype "passive"))
      (node (ref "R10") (pin "2") (pinfunction "2_2") (pintype "passive"))
    )
    (net (code "47") (name "Net-(LED6-C)") (class "Default")
      (node (ref "LED6") (pin "K") (pinfunction "C_K") (pintype "passive"))
      (node (ref "T5") (pin "2") (pinfunction "B_2") (pintype "passive"))
    )
    (net (code "48") (name "Net-(LED6-PadA)") (class "Default")
      (node (ref "LED6") (pin "A") (pinfunction "A_A") (pintype "passive"))
      (node (ref "R11") (pin "2") (pinfunction "2_2") (pintype "passive"))
    )
    (net (code "49") (name "Net-(LED7-C)") (class "Default")
      (node (ref "LED7") (pin "K") (pinfunction "C_K") (pintype "passive"))
      (node (ref "T6") (pin "2") (pinfunction "B_2") (pintype "passive"))
    )
    (net (code "50") (name "Net-(LED7-PadA)") (class "Default")
      (node (ref "LED7") (pin "A") (pinfunction "A_A") (pintype "passive"))
      (node (ref "R12") (pin "2") (pinfunction "2_2") (pintype "passive"))
    )
    (net (code "51") (name "Net-(LED8-C)") (class "Default")
      (node (ref "LED8") (pin "K") (pinfunction "C_K") (pintype "passive"))
      (node (ref "T7") (pin "2") (pinfunction "B_2") (pintype "passive"))
    )
    (net (code "52") (name "Net-(LED8-PadA)") (class "Default")
      (node (ref "LED8") (pin "A") (pinfunction "A_A") (pintype "passive"))
      (node (ref "R13") (pin "2") (pinfunction "2_2") (pintype "passive"))
    )
    (net (code "53") (name "Net-(LED9-C)") (class "Default")
      (node (ref "LED9") (pin "K") (pinfunction "C_K") (pintype "passive"))
      (node (ref "T8") (pin "2") (pinfunction "B_2") (pintype "passive"))
    )
    (net (code "54") (name "Net-(LED9-PadA)") (class "Default")
      (node (ref "LED9") (pin "A") (pinfunction "A_A") (pintype "passive"))
      (node (ref "R14") (pin "2") (pinfunction "2_2") (pintype "passive"))
    )
    (net (code "55") (name "Net-(LED10-PadA)") (class "Default")
      (node (ref "LED10") (pin "A") (pinfunction "A_A") (pintype "passive"))
      (node (ref "R15") (pin "1") (pinfunction "1_1") (pintype "passive"))
    )
    (net (code "56") (name "Net-(LED11-PadA)") (class "Default")
      (node (ref "LED11") (pin "A") (pinfunction "A_A") (pintype "passive"))
      (node (ref "R18") (pin "1") (pinfunction "1_1") (pintype "passive"))
    )
    (net (code "57") (name "Net-(LED12-PadA)") (class "Default")
      (node (ref "LED12") (pin "A") (pinfunction "A_A") (pintype "passive"))
      (node (ref "R21") (pin "1") (pinfunction "1_1") (pintype "passive"))
    )
    (net (code "58") (name "Net-(LED13-PadA)") (class "Default")
      (node (ref "LED13") (pin "A") (pinfunction "A_A") (pintype "passive"))
      (node (ref "R24") (pin "1") (pinfunction "1_1") (pintype "passive"))
    )
    (net (code "59") (name "Net-(LED14-PadA)") (class "Default")
      (node (ref "LED14") (pin "A") (pinfunction "A_A") (pintype "passive"))
      (node (ref "R27") (pin "1") (pinfunction "1_1") (pintype "passive"))
    )
    (net (code "60") (name "Net-(LED15-PadA)") (class "Default")
      (node (ref "LED15") (pin "A") (pinfunction "A_A") (pintype "passive"))
      (node (ref "R30") (pin "1") (pinfunction "1_1") (pintype "passive"))
    )
    (net (code "61") (name "Net-(LED16-PadA)") (class "Default")
      (node (ref "LED16") (pin "A") (pinfunction "A_A") (pintype "passive"))
      (node (ref "R33") (pin "1") (pinfunction "1_1") (pintype "passive"))
    )
    (net (code "62") (name "Net-(LED17-PadA)") (class "Default")
      (node (ref "LED17") (pin "A") (pinfunction "A_A") (pintype "passive"))
      (node (ref "R36") (pin "1") (pinfunction "1_1") (pintype "passive"))
    )
    (net (code "63") (name "Net-(OK2-A)") (class "Default")
      (node (ref "OK2") (pin "1") (pinfunction "A_1") (pintype "passive"))
      (node (ref "R16") (pin "1") (pinfunction "1_1") (pintype "passive"))
    )
    (net (code "64") (name "Net-(OK2-COL)") (class "Default")
      (node (ref "OK2") (pin "4") (pinfunction "COL_4") (pintype "passive"))
      (node (ref "R17") (pin "2") (pinfunction "2_2") (pintype "passive"))
      (node (ref "U$1") (pin "A0") (pinfunction "A0_A0") (pintype "bidirectional"))
    )
    (net (code "65") (name "Net-(OK3-A)") (class "Default")
      (node (ref "OK3") (pin "1") (pinfunction "A_1") (pintype "passive"))
      (node (ref "R19") (pin "1") (pinfunction "1_1") (pintype "passive"))
    )
    (net (code "66") (name "Net-(OK3-COL)") (class "Default")
      (node (ref "OK3") (pin "4") (pinfunction "COL_4") (pintype "passive"))
      (node (ref "R20") (pin "2") (pinfunction "2_2") (pintype "passive"))
      (node (ref "U$1") (pin "A1") (pinfunction "A1_A1") (pintype "bidirectional"))
    )
    (net (code "67") (name "Net-(OK4-A)") (class "Default")
      (node (ref "OK4") (pin "1") (pinfunction "A_1") (pintype "passive"))
      (node (ref "R22") (pin "1") (pinfunction "1_1") (pintype "passive"))
    )
    (net (code "68") (name "Net-(OK4-COL)") (class "Default")
      (node (ref "OK4") (pin "4") (pinfunction "COL_4") (pintype "passive"))
      (node (ref "R23") (pin "2") (pinfunction "2_2") (pintype "passive"))
      (node (ref "U$1") (pin "A2") (pinfunction "A2_A2") (pintype "bidirectional"))
    )
    (net (code "69") (name "Net-(OK5-A)") (class "Default")
      (node (ref "OK5") (pin "1") (pinfunction "A_1") (pintype "passive"))
      (node (ref "R25") (pin "1") (pinfunction "1_1") (pintype "passive"))
    )
    (net (code "70") (name "Net-(OK5-COL)") (class "Default")
      (node (ref "OK5") (pin "4") (pinfunction "COL_4") (pintype "passive"))
      (node (ref "R26") (pin "2") (pinfunction "2_2") (pintype "passive"))
      (node (ref "U$1") (pin "A3") (pinfunction "A3_A3") (pintype "bidirectional"))
    )
    (net (code "71") (name "Net-(OK6-A)") (class "Default")
      (node (ref "OK6") (pin "1") (pinfunction "A_1") (pintype "passive"))
      (node (ref "R28") (pin "1") (pinfunction "1_1") (pintype "passive"))
    )
    (net (code "72") (name "Net-(OK6-COL)") (class "Default")
      (node (ref "OK6") (pin "4") (pinfunction "COL_4") (pintype "passive"))
      (node (ref "R29") (pin "2") (pinfunction "2_2") (pintype "passive"))
      (node (ref "U$1") (pin "A4") (pinfunction "A4_A4") (pintype "bidirectional"))
    )
    (net (code "73") (name "Net-(OK7-A)") (class "Default")
      (node (ref "OK7") (pin "1") (pinfunction "A_1") (pintype "passive"))
      (node (ref "R31") (pin "1") (pinfunction "1_1") (pintype "passive"))
    )
    (net (code "74") (name "Net-(OK7-COL)") (class "Default")
      (node (ref "OK7") (pin "4") (pinfunction "COL_4") (pintype "passive"))
      (node (ref "R32") (pin "2") (pinfunction "2_2") (pintype "passive"))
      (node (ref "U$1") (pin "A5") (pinfunction "A5_A5") (pintype "bidirectional"))
    )
    (net (code "75") (name "Net-(OK8-A)") (class "Default")
      (node (ref "OK8") (pin "1") (pinfunction "A_1") (pintype "passive"))
      (node (ref "R34") (pin "1") (pinfunction "1_1") (pintype "passive"))
    )
    (net (code "76") (name "Net-(OK8-COL)") (class "Default")
      (node (ref "OK8") (pin "4") (pinfunction "COL_4") (pintype "passive"))
      (node (ref "R35") (pin "2") (pinfunction "2_2") (pintype "passive"))
      (node (ref "U$1") (pin "A6") (pinfunction "A6_A6") (pintype "bidirectional"))
    )
    (net (code "77") (name "Net-(OK9-A)") (class "Default")
      (node (ref "OK9") (pin "1") (pinfunction "A_1") (pintype "passive"))
      (node (ref "R37") (pin "1") (pinfunction "1_1") (pintype "passive"))
    )
    (net (code "78") (name "Net-(OK9-COL)") (class "Default")
      (node (ref "OK9") (pin "4") (pinfunction "COL_4") (pintype "passive"))
      (node (ref "R38") (pin "2") (pinfunction "2_2") (pintype "passive"))
      (node (ref "U$1") (pin "A7") (pinfunction "A7_A7") (pintype "bidirectional"))
    )
    (net (code "79") (name "Net-(R7-Pad1)") (class "Default")
      (node (ref "R7") (pin "1") (pinfunction "1_1") (pintype "passive"))
      (node (ref "U$1") (pin "D9") (pinfunction "D9_D9") (pintype "bidirectional"))
    )
    (net (code "80") (name "Net-(R8-Pad1)") (class "Default")
      (node (ref "R8") (pin "1") (pinfunction "1_1") (pintype "passive"))
      (node (ref "U$1") (pin "D8") (pinfunction "D8_D8") (pintype "bidirectional"))
    )
    (net (code "81") (name "Net-(R9-Pad1)") (class "Default")
      (node (ref "R9") (pin "1") (pinfunction "1_1") (pintype "passive"))
      (node (ref "U$1") (pin "D7") (pinfunction "D7_D7") (pintype "bidirectional"))
    )
    (net (code "82") (name "Net-(R10-Pad1)") (class "Default")
      (node (ref "R10") (pin "1") (pinfunction "1_1") (pintype "passive"))
      (node (ref "U$1") (pin "D6") (pinfunction "D6_D6") (pintype "bidirectional"))
    )
    (net (code "83") (name "Net-(R11-Pad1)") (class "Default")
      (node (ref "R11") (pin "1") (pinfunction "1_1") (pintype "passive"))
      (node (ref "U$1") (pin "D5") (pinfunction "D5_D5") (pintype "bidirectional"))
    )
    (net (code "84") (name "Net-(R12-Pad1)") (class "Default")
      (node (ref "R12") (pin "1") (pinfunction "1_1") (pintype "passive"))
      (node (ref "U$1") (pin "D4") (pinfunction "D4_D4") (pintype "bidirectional"))
    )
    (net (code "85") (name "Net-(R13-Pad1)") (class "Default")
      (node (ref "R13") (pin "1") (pinfunction "1_1") (pintype "passive"))
      (node (ref "U$1") (pin "D3") (pinfunction "D3_D3") (pintype "bidirectional"))
    )
    (net (code "86") (name "Net-(R14-Pad1)") (class "Default")
      (node (ref "R14") (pin "1") (pinfunction "1_1") (pintype "passive"))
      (node (ref "U$1") (pin "D2") (pinfunction "D2_D2") (pintype "bidirectional"))
    )
    (net (code "87") (name "Net-(T1-C)") (class "Default")
      (node (ref "D2") (pin "A") (pinfunction "A_A") (pintype "passive"))
      (node (ref "K2") (pin "2") (pinfunction "2_2") (pintype "passive"))
      (node (ref "T1") (pin "3") (pinfunction "C_3") (pintype "passive"))
    )
    (net (code "88") (name "Net-(T1-E)") (class "Default")
      (node (ref "T1") (pin "1") (pinfunction "E_1") (pintype "passive"))
      (node (ref "T2") (pin "1") (pinfunction "E_1") (pintype "passive"))
      (node (ref "T3") (pin "1") (pinfunction "E_1") (pintype "passive"))
      (node (ref "T4") (pin "1") (pinfunction "E_1") (pintype "passive"))
      (node (ref "T5") (pin "1") (pinfunction "E_1") (pintype "passive"))
      (node (ref "T6") (pin "1") (pinfunction "E_1") (pintype "passive"))
      (node (ref "T7") (pin "1") (pinfunction "E_1") (pintype "passive"))
      (node (ref "T8") (pin "1") (pinfunction "E_1") (pintype "passive"))
    )
    (net (code "89") (name "Net-(T2-C)") (class "Default")
      (node (ref "D3") (pin "A") (pinfunction "A_A") (pintype "passive"))
      (node (ref "K1") (pin "2") (pinfunction "2_2") (pintype "passive"))
      (node (ref "T2") (pin "3") (pinfunction "C_3") (pintype "passive"))
    )
    (net (code "90") (name "Net-(T3-C)") (class "Default")
      (node (ref "D4") (pin "A") (pinfunction "A_A") (pintype "passive"))
      (node (ref "K3") (pin "2") (pinfunction "2_2") (pintype "passive"))
      (node (ref "T3") (pin "3") (pinfunction "C_3") (pintype "passive"))
    )
    (net (code "91") (name "Net-(T4-C)") (class "Default")
      (node (ref "D5") (pin "A") (pinfunction "A_A") (pintype "passive"))
      (node (ref "K4") (pin "2") (pinfunction "2_2") (pintype "passive"))
      (node (ref "T4") (pin "3") (pinfunction "C_3") (pintype "passive"))
    )
    (net (code "92") (name "Net-(T5-C)") (class "Default")
      (node (ref "D6") (pin "A") (pinfunction "A_A") (pintype "passive"))
      (node (ref "K5") (pin "2") (pinfunction "2_2") (pintype "passive"))
      (node (ref "T5") (pin "3") (pinfunction "C_3") (pintype "passive"))
    )
    (net (code "93") (name "Net-(T6-C)") (class "Default")
      (node (ref "D7") (pin "A") (pinfunction "A_A") (pintype "passive"))
      (node (ref "K6") (pin "2") (pinfunction "2_2") (pintype "passive"))
      (node (ref "T6") (pin "3") (pinfunction "C_3") (pintype "passive"))
    )
    (net (code "94") (name "Net-(T7-C)") (class "Default")
      (node (ref "D8") (pin "A") (pinfunction "A_A") (pintype "passive"))
      (node (ref "K7") (pin "2") (pinfunction "2_2") (pintype "passive"))
      (node (ref "T7") (pin "3") (pinfunction "C_3") (pintype "passive"))
    )
    (net (code "95") (name "Net-(T8-C)") (class "Default")
      (node (ref "D9") (pin "A") (pinfunction "A_A") (pintype "passive"))
      (node (ref "K8") (pin "2") (pinfunction "2_2") (pintype "passive"))
      (node (ref "T8") (pin "3") (pinfunction "C_3") (pintype "passive"))
    )
    (net (code "96") (name "unconnected-(U$1-5.5V-Pad5V)") (class "Default")
      (node (ref "U$1") (pin "5V") (pinfunction "5.5V_5V") (pintype "bidirectional"))
    )
    (net (code "97") (name "unconnected-(U$1-GND2-PadGND1)") (class "Default")
      (node (ref "U$1") (pin "GND1") (pinfunction "GND2_GND1") (pintype "bidirectional"))
    )
    (net (code "98") (name "unconnected-(U$1-Pad3.3V)") (class "Default")
      (node (ref "U$1") (pin "3.3V") (pinfunction "3.3V_3.3V") (pintype "bidirectional"))
    )
    (net (code "99") (name "unconnected-(U$1-PadAREF)") (class "Default")
      (node (ref "U$1") (pin "AREF") (pinfunction "AREF_AREF") (pintype "bidirectional"))
    )
    (net (code "100") (name "unconnected-(U$1-PadD10)") (class "Default")
      (node (ref "U$1") (pin "D10") (pinfunction "D10_D10") (pintype "bidirectional"))
    )
    (net (code "101") (name "unconnected-(U$1-PadD11)") (class "Default")
      (node (ref "U$1") (pin "D11") (pinfunction "D11_D11") (pintype "bidirectional"))
    )
    (net (code "102") (name "unconnected-(U$1-PadD12)") (class "Default")
      (node (ref "U$1") (pin "D12") (pinfunction "D12_D12") (pintype "bidirectional"))
    )
    (net (code "103") (name "unconnected-(U$1-PadD13)") (class "Default")
      (node (ref "U$1") (pin "D13") (pinfunction "D13_D13") (pintype "bidirectional"))
    )
    (net (code "104") (name "unconnected-(U$1-PadICSP1)") (class "Default")
      (node (ref "U$1") (pin "ICSP1") (pinfunction "ICSP1_ICSP1") (pintype "bidirectional"))
    )
    (net (code "105") (name "unconnected-(U$1-PadICSP2)") (class "Default")
      (node (ref "U$1") (pin "ICSP2") (pinfunction "ICSP2_ICSP2") (pintype "bidirectional"))
    )
    (net (code "106") (name "unconnected-(U$1-PadICSP3)") (class "Default")
      (node (ref "U$1") (pin "ICSP3") (pinfunction "ICSP3_ICSP3") (pintype "bidirectional"))
    )
    (net (code "107") (name "unconnected-(U$1-PadICSP4)") (class "Default")
      (node (ref "U$1") (pin "ICSP4") (pinfunction "ICSP4_ICSP4") (pintype "bidirectional"))
    )
    (net (code "108") (name "unconnected-(U$1-PadICSP5)") (class "Default")
      (node (ref "U$1") (pin "ICSP5") (pinfunction "ICSP5_ICSP5") (pintype "bidirectional"))
    )
    (net (code "109") (name "unconnected-(U$1-PadICSP6)") (class "Default")
      (node (ref "U$1") (pin "ICSP6") (pinfunction "ICSP6_ICSP6") (pintype "bidirectional"))
    )
    (net (code "110") (name "unconnected-(U$1-PadRST)") (class "Default")
      (node (ref "U$1") (pin "RST") (pinfunction "RST_RST") (pintype "bidirectional"))
    )
    (net (code "111") (name "unconnected-(U$1-PadRST1)") (class "Default")
      (node (ref "U$1") (pin "RST1") (pinfunction "RST1_RST1") (pintype "bidirectional"))
    )
    (net (code "112") (name "unconnected-(U$1-PadRX1)") (class "Default")
      (node (ref "U$1") (pin "RX1") (pinfunction "RX1_RX1") (pintype "bidirectional"))
    )
    (net (code "113") (name "unconnected-(U$1-PadTX0)") (class "Default")
      (node (ref "U$1") (pin "TX0") (pinfunction "TX0_TX0") (pintype "bidirectional"))
    )
  )
)
